# gnss_quectel_lc29hea.net
KiCad netlist of a schematic drawn in Altium Designer
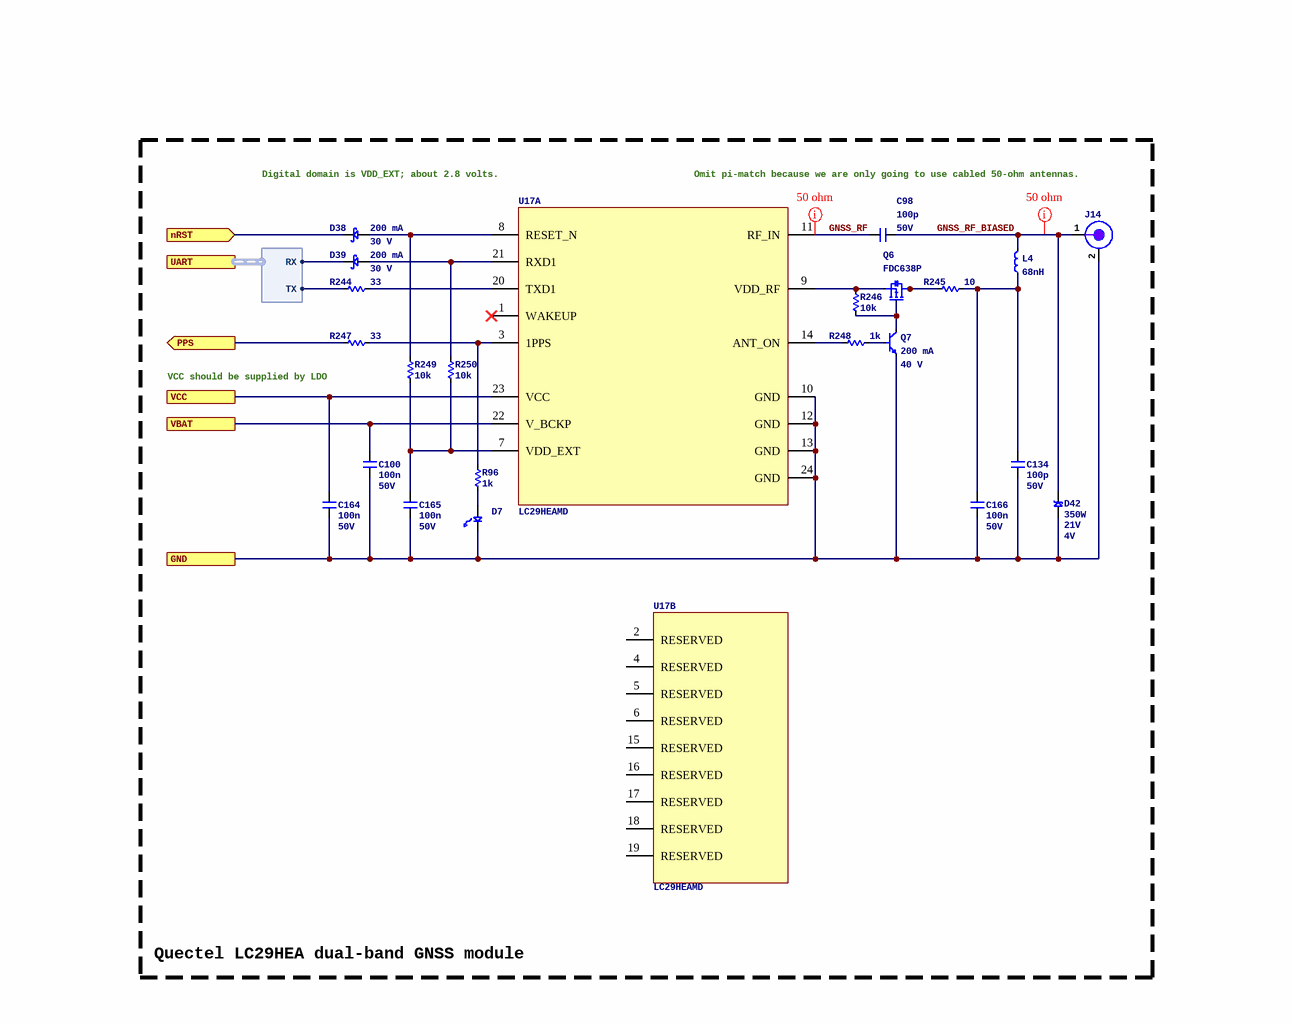
[diagram p0: gnss_quectel_lc29hea.SchDoc]

(export (version "E")
  (design (tool "Eeschema 10.0.6"))
  (components
    (comp (ref "C98")
      (value "0402CG101J500NT")
      (footprint "C0402")
      (fields
        (field (name "CAPACITANCE") "100p")
        (field (name "MANUFACTURER") "FH(Guangdong Fenghua Advanced Tech)")
        (field (name "VOLTAGE RATING") "50V")
      )
      (libsource (lib "database") (part "__template_cap"))
    )
    (comp (ref "C100")
      (value "CL05B104KB54PNC")
      (footprint "C0402")
      (fields
        (field (name "CAPACITANCE") "100n")
        (field (name "MANUFACTURER") "Samsung Electro-Mechanics")
        (field (name "VOLTAGE RATING") "50V")
      )
      (libsource (lib "database") (part "__template_cap"))
    )
    (comp (ref "C134")
      (value "0402CG101J500NT")
      (footprint "C0402")
      (fields
        (field (name "CAPACITANCE") "100p")
        (field (name "MANUFACTURER") "FH(Guangdong Fenghua Advanced Tech)")
        (field (name "VOLTAGE RATING") "50V")
      )
      (libsource (lib "database") (part "__template_cap"))
    )
    (comp (ref "C164")
      (value "CL05B104KB54PNC")
      (footprint "C0402")
      (fields
        (field (name "CAPACITANCE") "100n")
        (field (name "MANUFACTURER") "Samsung Electro-Mechanics")
        (field (name "VOLTAGE RATING") "50V")
      )
      (libsource (lib "database") (part "__template_cap"))
    )
    (comp (ref "C165")
      (value "CL05B104KB54PNC")
      (footprint "C0402")
      (fields
        (field (name "CAPACITANCE") "100n")
        (field (name "MANUFACTURER") "Samsung Electro-Mechanics")
        (field (name "VOLTAGE RATING") "50V")
      )
      (libsource (lib "database") (part "__template_cap"))
    )
    (comp (ref "C166")
      (value "CL05B104KB54PNC")
      (footprint "C0402")
      (fields
        (field (name "CAPACITANCE") "100n")
        (field (name "MANUFACTURER") "Samsung Electro-Mechanics")
        (field (name "VOLTAGE RATING") "50V")
      )
      (libsource (lib "database") (part "__template_cap"))
    )
    (comp (ref "D7")
      (value "LTST-C191TBKT")
      (footprint "LED_0603P_BLUE")
      (description "LED 468NM BLUE CLEAR 0603 SMD")
      (fields (field (name "MANUFACTURER") "Lite-On Inc"))
      (libsource (lib "SSCP") (part "LED_0603_BLUE_LTST-C191TBKT"))
    )
    (comp (ref "D38")
      (value "BAT54XV2T1G")
      (footprint "SOD523")
      (description "ON Semi BAT54XV2T1G; SMT Schottky Diode; 30V 200mA; 5ns; 2-Pin SOD-523")
      (fields
        (field (name "MANUFACTURER") "onsemi")
        (field (name "CURRENT") "200 mA")
        (field (name "VOLTAGE") "30 V")
      )
      (libsource (lib "SSCP") (part "SCHOTTKY_30V_BAT54XV2T1G"))
    )
    (comp (ref "D39")
      (value "BAT54XV2T1G")
      (footprint "SOD523")
      (description "ON Semi BAT54XV2T1G; SMT Schottky Diode; 30V 200mA; 5ns; 2-Pin SOD-523")
      (fields
        (field (name "MANUFACTURER") "onsemi")
        (field (name "CURRENT") "200 mA")
        (field (name "VOLTAGE") "30 V")
      )
      (libsource (lib "SSCP") (part "SCHOTTKY_30V_BAT54XV2T1G"))
    )
    (comp (ref "D42")
      (value "PTVSLC3D3V3B")
      (footprint "SOD323")
      (fields
        (field (name "MANUFACTURER") "Prisemi")
        (field (name "NON-REP PEAK REV POWER DIS-MAX") "350W")
        (field (name "CLAMPING VOLTAGE-MAX") "21V")
        (field (name "MIN BREAKDOWN VOLTAGE") "4V")
      )
      (libsource (lib "SSCP") (part "TVS_UNI_3.3V_PTVSLC3D3V3B"))
    )
    (comp (ref "J14")
      (value "RFPC-SMA14-FN-A")
      (footprint "GCT_RFPC-SMA14-FN-A")
      (description "SMA Connector Jack, Female Socket Panel Mount, Through Hole, Right Angle Solder, IP68 unmated")
      (fields (field (name "MANUFACTURER") "GCT (Gradconn)"))
      (libsource (lib "SSCP") (part "CONN_GCT_SMA_RA_RFPC-SMA14-FN-A"))
    )
    (comp (ref "L4")
      (value "68nH")
      (footprint "L0603_0.95MM")
      (fields
        (field (name "MANUFACTURER") "Murata")
        (field (name "MANUFACTURER PART NUMBER") "LQW18AN68NJ80D")
      )
      (libsource (lib "SSCP") (part "IND_0.068UH_LQW18AN68NJ80D"))
    )
    (comp (ref "Q6")
      (value "FDC638P")
      (footprint "6SOT23")
      (description "MOSFET P-CH 20V 4.5A SSOT-6")
      (fields (field (name "MANUFACTURER") "onsemi"))
      (libsource (lib "SSCP") (part "PFET_20V_FDC638P"))
    )
    (comp (ref "Q7")
      (value "MMBT3904T")
      (footprint "3SOT523")
      (description "Bipolar (BJT) Transistor NPN 40 V 200 mA 300MHz 150 mW Surface Mount SOT-523")
      (fields
        (field (name "MANUFACTURER") "Shenzhen Slkormicro Semicon Co., Ltd.")
        (field (name "CURRENT") "200 mA")
        (field (name "VOLTAGE") "40 V")
      )
      (libsource (lib "SSCP") (part "NPN_40V_MMBT3904T"))
    )
    (comp (ref "R96")
      (value "1k")
      (footprint "R0402")
      (fields
        (field (name "TOLERANCE") "1%")
        (field (name "MANUFACTURER PART NUMBER") "0402WGF1001TCE")
        (field (name "MANUFACTURER") "UNI-ROYAL(Uniroyal Elec)")
      )
      (libsource (lib "database") (part "__template_resistor"))
    )
    (comp (ref "R244")
      (value "33")
      (footprint "R0402")
      (fields
        (field (name "TOLERANCE") "1%")
        (field (name "MANUFACTURER PART NUMBER") "0402WGF330JTCE")
        (field (name "MANUFACTURER") "UNI-ROYAL(Uniroyal Elec)")
      )
      (libsource (lib "database") (part "__template_resistor"))
    )
    (comp (ref "R245")
      (value "10")
      (footprint "R2512")
      (fields
        (field (name "TOLERANCE") "1%")
        (field (name "MANUFACTURER PART NUMBER") "RTT2510R0FTE")
        (field (name "MANUFACTURER") "RALEC")
      )
      (libsource (lib "database") (part "__template_resistor"))
    )
    (comp (ref "R246")
      (value "10k")
      (footprint "R0402")
      (fields
        (field (name "TOLERANCE") "1%")
        (field (name "MANUFACTURER PART NUMBER") "0402WGF1002TCE")
        (field (name "MANUFACTURER") "UNI-ROYAL(Uniroyal Elec)")
      )
      (libsource (lib "database") (part "__template_resistor"))
    )
    (comp (ref "R247")
      (value "33")
      (footprint "R0402")
      (fields
        (field (name "TOLERANCE") "1%")
        (field (name "MANUFACTURER PART NUMBER") "0402WGF330JTCE")
        (field (name "MANUFACTURER") "UNI-ROYAL(Uniroyal Elec)")
      )
      (libsource (lib "database") (part "__template_resistor"))
    )
    (comp (ref "R248")
      (value "1k")
      (footprint "R0402")
      (fields
        (field (name "TOLERANCE") "1%")
        (field (name "MANUFACTURER PART NUMBER") "0402WGF1001TCE")
        (field (name "MANUFACTURER") "UNI-ROYAL(Uniroyal Elec)")
      )
      (libsource (lib "database") (part "__template_resistor"))
    )
    (comp (ref "R249")
      (value "10k")
      (footprint "R0402")
      (fields
        (field (name "TOLERANCE") "1%")
        (field (name "MANUFACTURER PART NUMBER") "0402WGF1002TCE")
        (field (name "MANUFACTURER") "UNI-ROYAL(Uniroyal Elec)")
      )
      (libsource (lib "database") (part "__template_resistor"))
    )
    (comp (ref "R250")
      (value "10k")
      (footprint "R0402")
      (fields
        (field (name "TOLERANCE") "1%")
        (field (name "MANUFACTURER PART NUMBER") "0402WGF1002TCE")
        (field (name "MANUFACTURER") "UNI-ROYAL(Uniroyal Elec)")
      )
      (libsource (lib "database") (part "__template_resistor"))
    )
    (comp (ref "U17")
      (value "LC29HEAMD")
      (footprint "QUECTEL_LC29H")
      (description "Rf Txrx Module Navigation SMD")
      (fields (field (name "MANUFACTURER") "Quectel"))
      (libsource (lib "SSCP") (part "GNSS_QUECTEL_LC29HEAMD"))
    )
  )
  (nets
    (net (code "2") (name "/GND") (class "Default")
      (node (ref "C100") (pin "2") (pintype "passive"))
      (node (ref "C134") (pin "2") (pintype "passive"))
      (node (ref "C164") (pin "2") (pintype "passive"))
      (node (ref "C165") (pin "2") (pintype "passive"))
      (node (ref "C166") (pin "2") (pintype "passive"))
      (node (ref "D42") (pin "1") (pintype "passive"))
      (node (ref "D7") (pin "1") (pintype "passive"))
      (node (ref "J14") (pin "2") (pinfunction "GND_2") (pintype "passive"))
      (node (ref "Q7") (pin "2") (pinfunction "E_2") (pintype "passive"))
      (node (ref "U17") (pin "10") (pinfunction "GND_10") (pintype "passive"))
      (node (ref "U17") (pin "12") (pinfunction "GND_12") (pintype "passive"))
      (node (ref "U17") (pin "13") (pinfunction "GND_13") (pintype "passive"))
      (node (ref "U17") (pin "24") (pinfunction "GND_24") (pintype "passive"))
    )
    (net (code "3") (name "/GNSS_RF") (class "Default")
      (node (ref "C98") (pin "1") (pintype "passive"))
      (node (ref "U17") (pin "11") (pinfunction "RF_IN_11") (pintype "passive"))
    )
    (net (code "4") (name "/GNSS_RF_BIASED") (class "Default")
      (node (ref "C98") (pin "2") (pintype "passive"))
      (node (ref "D42") (pin "2") (pintype "passive"))
      (node (ref "J14") (pin "1") (pinfunction "RF_1") (pintype "passive"))
      (node (ref "L4") (pin "2") (pintype "passive"))
    )
    (net (code "5") (name "/PPS") (class "Default") (node (ref "R247") (pin "2") (pintype "passive")))
    (net (code "6") (name "/RX") (class "Default") (node (ref "D39") (pin "2") (pintype "passive")))
    (net (code "7") (name "/TX") (class "Default") (node (ref "R244") (pin "2") (pintype "passive")))
    (net (code "8") (name "/VBAT") (class "Default")
      (node (ref "C100") (pin "1") (pintype "passive"))
      (node (ref "U17") (pin "22") (pinfunction "V_BCKP_22") (pintype "passive"))
    )
    (net (code "9") (name "/VCC") (class "Default")
      (node (ref "C164") (pin "1") (pintype "passive"))
      (node (ref "U17") (pin "23") (pinfunction "VCC_23") (pintype "passive"))
    )
    (net (code "10") (name "/nRST") (class "Default") (node (ref "D38") (pin "2") (pintype "passive")))
    (net (code "12") (name "Net-(C134-Pad1)") (class "Default")
      (node (ref "C134") (pin "1") (pintype "passive"))
      (node (ref "C166") (pin "1") (pintype "passive"))
      (node (ref "L4") (pin "1") (pintype "passive"))
      (node (ref "R245") (pin "1") (pintype "passive"))
    )
    (net (code "13") (name "Net-(D7-Pad2)") (class "Default")
      (node (ref "D7") (pin "2") (pintype "passive"))
      (node (ref "R96") (pin "2") (pintype "passive"))
    )
    (net (code "14") (name "Net-(Q6-Pad1)") (class "Default")
      (node (ref "Q6") (pin "1") (pintype "passive"))
      (node (ref "Q6") (pin "2") (pintype "passive"))
      (node (ref "Q6") (pin "5") (pintype "passive"))
      (node (ref "Q6") (pin "6") (pintype "passive"))
      (node (ref "R245") (pin "2") (pintype "passive"))
    )
    (net (code "15") (name "Net-(Q7-B)") (class "Default")
      (node (ref "Q7") (pin "1") (pinfunction "B_1") (pintype "passive"))
      (node (ref "R248") (pin "1") (pintype "passive"))
    )
    (net (code "16") (name "Net-(Q7-C)") (class "Default")
      (node (ref "Q6") (pin "3") (pintype "passive"))
      (node (ref "Q7") (pin "3") (pinfunction "C_3") (pintype "passive"))
      (node (ref "R246") (pin "2") (pintype "passive"))
    )
    (net (code "17") (name "Net-(U17A-1PPS)") (class "Default")
      (node (ref "R247") (pin "1") (pintype "passive"))
      (node (ref "R96") (pin "1") (pintype "passive"))
      (node (ref "U17") (pin "3") (pinfunction "1PPS_3") (pintype "passive"))
    )
    (net (code "18") (name "Net-(U17A-ANT_ON)") (class "Default")
      (node (ref "R248") (pin "2") (pintype "passive"))
      (node (ref "U17") (pin "14") (pinfunction "ANT_ON_14") (pintype "passive"))
    )
    (net (code "19") (name "Net-(U17A-RESET_N)") (class "Default")
      (node (ref "D38") (pin "1") (pintype "passive"))
      (node (ref "R249") (pin "1") (pintype "passive"))
      (node (ref "U17") (pin "8") (pinfunction "RESET_N_8") (pintype "passive"))
    )
    (net (code "20") (name "Net-(U17A-RXD1)") (class "Default")
      (node (ref "D39") (pin "1") (pintype "passive"))
      (node (ref "R250") (pin "1") (pintype "passive"))
      (node (ref "U17") (pin "21") (pinfunction "RXD1_21") (pintype "passive"))
    )
    (net (code "21") (name "Net-(U17A-TXD1)") (class "Default")
      (node (ref "R244") (pin "1") (pintype "passive"))
      (node (ref "U17") (pin "20") (pinfunction "TXD1_20") (pintype "passive"))
    )
    (net (code "22") (name "Net-(U17A-VDD_EXT)") (class "Default")
      (node (ref "C165") (pin "1") (pintype "passive"))
      (node (ref "R249") (pin "2") (pintype "passive"))
      (node (ref "R250") (pin "2") (pintype "passive"))
      (node (ref "U17") (pin "7") (pinfunction "VDD_EXT_7") (pintype "passive"))
    )
    (net (code "23") (name "Net-(U17A-VDD_RF)") (class "Default")
      (node (ref "Q6") (pin "4") (pintype "passive"))
      (node (ref "R246") (pin "1") (pintype "passive"))
      (node (ref "U17") (pin "9") (pinfunction "VDD_RF_9") (pintype "passive"))
    )
    (net (code "24") (name "unconnected-(U17A-WAKEUP-Pad1)") (class "Default")
      (node (ref "U17") (pin "1") (pinfunction "WAKEUP_1") (pintype "passive+no_connect"))
    )
    (net (code "25") (name "unconnected-(U17B-RESERVED-Pad2)") (class "Default")
      (node (ref "U17") (pin "2") (pinfunction "RESERVED_2") (pintype "passive"))
    )
    (net (code "26") (name "unconnected-(U17B-RESERVED-Pad4)") (class "Default")
      (node (ref "U17") (pin "4") (pinfunction "RESERVED_4") (pintype "passive"))
    )
    (net (code "27") (name "unconnected-(U17B-RESERVED-Pad5)") (class "Default")
      (node (ref "U17") (pin "5") (pinfunction "RESERVED_5") (pintype "passive"))
    )
    (net (code "28") (name "unconnected-(U17B-RESERVED-Pad6)") (class "Default")
      (node (ref "U17") (pin "6") (pinfunction "RESERVED_6") (pintype "passive"))
    )
    (net (code "29") (name "unconnected-(U17B-RESERVED-Pad15)") (class "Default")
      (node (ref "U17") (pin "15") (pinfunction "RESERVED_15") (pintype "passive"))
    )
    (net (code "30") (name "unconnected-(U17B-RESERVED-Pad16)") (class "Default")
      (node (ref "U17") (pin "16") (pinfunction "RESERVED_16") (pintype "passive"))
    )
    (net (code "31") (name "unconnected-(U17B-RESERVED-Pad17)") (class "Default")
      (node (ref "U17") (pin "17") (pinfunction "RESERVED_17") (pintype "passive"))
    )
    (net (code "32") (name "unconnected-(U17B-RESERVED-Pad18)") (class "Default")
      (node (ref "U17") (pin "18") (pinfunction "RESERVED_18") (pintype "passive"))
    )
    (net (code "33") (name "unconnected-(U17B-RESERVED-Pad19)") (class "Default")
      (node (ref "U17") (pin "19") (pinfunction "RESERVED_19") (pintype "passive"))
    )
  )
)
